# splitter157.net
KiCad netlist of a schematic drawn in EAGLE
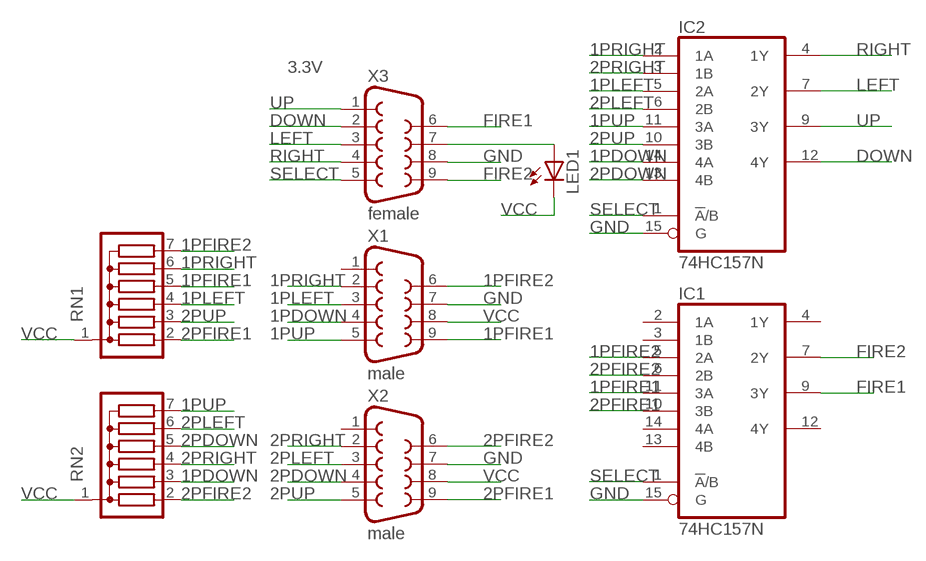
[diagram p0: schematic, sheet 1]

(export (version "E")
  (design (tool "Eeschema 10.0.6"))
  (components
    (comp (ref "IC1")
      (value "74HC157N")
      (footprint "eagle-import:DIL16NUEVO")
      (libsource (lib "eagle-import") (part "74157NHC"))
    )
    (comp (ref "IC2")
      (value "74HC157N")
      (footprint "eagle-import:DIL16NUEVO")
      (libsource (lib "eagle-import") (part "74157NHC"))
    )
    (comp (ref "LED1")
      (value "LED3MM")
      (footprint "eagle-import:LED3MM")
      (libsource (lib "eagle-import") (part "LED3MM"))
    )
    (comp (ref "RN1")
      (value "G06R")
      (footprint "eagle-import:SIL7")
      (libsource (lib "eagle-import") (part "G06R"))
    )
    (comp (ref "RN2")
      (value "G06R")
      (footprint "eagle-import:SIL7")
      (libsource (lib "eagle-import") (part "G06R"))
    )
    (comp (ref "X1")
      (value "male")
      (footprint "eagle-import:F09D")
      (libsource (lib "eagle-import") (part "F09D"))
    )
    (comp (ref "X2")
      (value "male")
      (footprint "eagle-import:F09D")
      (libsource (lib "eagle-import") (part "F09D"))
    )
    (comp (ref "X3")
      (value "female")
      (footprint "eagle-import:F09D")
      (libsource (lib "eagle-import") (part "F09D"))
    )
  )
  (nets
    (net (code "1") (name "/1PDOWN") (class "Default")
      (node (ref "IC2") (pin "14") (pinfunction "4A_14") (pintype "input"))
      (node (ref "RN2") (pin "3") (pinfunction "3_3") (pintype "passive"))
      (node (ref "X1") (pin "4") (pinfunction "4_4") (pintype "passive"))
    )
    (net (code "2") (name "/1PFIRE1") (class "Default")
      (node (ref "IC1") (pin "11") (pinfunction "3A_11") (pintype "input"))
      (node (ref "RN1") (pin "5") (pinfunction "5_5") (pintype "passive"))
      (node (ref "X1") (pin "9") (pinfunction "9_9") (pintype "passive"))
    )
    (net (code "3") (name "/1PFIRE2") (class "Default")
      (node (ref "IC1") (pin "5") (pinfunction "2A_5") (pintype "input"))
      (node (ref "RN1") (pin "7") (pinfunction "7_7") (pintype "passive"))
      (node (ref "X1") (pin "6") (pinfunction "6_6") (pintype "passive"))
    )
    (net (code "4") (name "/1PLEFT") (class "Default")
      (node (ref "IC2") (pin "5") (pinfunction "2A_5") (pintype "input"))
      (node (ref "RN1") (pin "4") (pinfunction "4_4") (pintype "passive"))
      (node (ref "X1") (pin "3") (pinfunction "3_3") (pintype "passive"))
    )
    (net (code "5") (name "/1PRIGHT") (class "Default")
      (node (ref "IC2") (pin "2") (pinfunction "1A_2") (pintype "input"))
      (node (ref "RN1") (pin "6") (pinfunction "6_6") (pintype "passive"))
      (node (ref "X1") (pin "2") (pinfunction "2_2") (pintype "passive"))
    )
    (net (code "6") (name "/1PUP") (class "Default")
      (node (ref "IC2") (pin "11") (pinfunction "3A_11") (pintype "input"))
      (node (ref "RN2") (pin "7") (pinfunction "7_7") (pintype "passive"))
      (node (ref "X1") (pin "5") (pinfunction "5_5") (pintype "passive"))
    )
    (net (code "7") (name "/2PDOWN") (class "Default")
      (node (ref "IC2") (pin "13") (pinfunction "4B_13") (pintype "input"))
      (node (ref "RN2") (pin "5") (pinfunction "5_5") (pintype "passive"))
      (node (ref "X2") (pin "4") (pinfunction "4_4") (pintype "passive"))
    )
    (net (code "8") (name "/2PFIRE1") (class "Default")
      (node (ref "IC1") (pin "10") (pinfunction "3B_10") (pintype "input"))
      (node (ref "RN1") (pin "2") (pinfunction "2_2") (pintype "passive"))
      (node (ref "X2") (pin "9") (pinfunction "9_9") (pintype "passive"))
    )
    (net (code "9") (name "/2PFIRE2") (class "Default")
      (node (ref "IC1") (pin "6") (pinfunction "2B_6") (pintype "input"))
      (node (ref "RN2") (pin "2") (pinfunction "2_2") (pintype "passive"))
      (node (ref "X2") (pin "6") (pinfunction "6_6") (pintype "passive"))
    )
    (net (code "10") (name "/2PLEFT") (class "Default")
      (node (ref "IC2") (pin "6") (pinfunction "2B_6") (pintype "input"))
      (node (ref "RN2") (pin "6") (pinfunction "6_6") (pintype "passive"))
      (node (ref "X2") (pin "3") (pinfunction "3_3") (pintype "passive"))
    )
    (net (code "11") (name "/2PRIGHT") (class "Default")
      (node (ref "IC2") (pin "3") (pinfunction "1B_3") (pintype "input"))
      (node (ref "RN2") (pin "4") (pinfunction "4_4") (pintype "passive"))
      (node (ref "X2") (pin "2") (pinfunction "2_2") (pintype "passive"))
    )
    (net (code "12") (name "/2PUP") (class "Default")
      (node (ref "IC2") (pin "10") (pinfunction "3B_10") (pintype "input"))
      (node (ref "RN1") (pin "3") (pinfunction "3_3") (pintype "passive"))
      (node (ref "X2") (pin "5") (pinfunction "5_5") (pintype "passive"))
    )
    (net (code "14") (name "/DOWN") (class "Default")
      (node (ref "IC2") (pin "12") (pinfunction "4Y_12") (pintype "output"))
      (node (ref "X3") (pin "2") (pinfunction "2_2") (pintype "passive"))
    )
    (net (code "15") (name "/FIRE1") (class "Default")
      (node (ref "IC1") (pin "9") (pinfunction "3Y_9") (pintype "output"))
      (node (ref "X3") (pin "6") (pinfunction "6_6") (pintype "passive"))
    )
    (net (code "16") (name "/FIRE2") (class "Default")
      (node (ref "IC1") (pin "7") (pinfunction "2Y_7") (pintype "output"))
      (node (ref "X3") (pin "9") (pinfunction "9_9") (pintype "passive"))
    )
    (net (code "17") (name "/GND") (class "Default")
      (node (ref "IC1") (pin "15") (pinfunction "G_15") (pintype "input"))
      (node (ref "IC2") (pin "15") (pinfunction "G_15") (pintype "input"))
      (node (ref "X1") (pin "7") (pinfunction "7_7") (pintype "passive"))
      (node (ref "X2") (pin "7") (pinfunction "7_7") (pintype "passive"))
      (node (ref "X3") (pin "8") (pinfunction "8_8") (pintype "passive"))
    )
    (net (code "18") (name "/LEFT") (class "Default")
      (node (ref "IC2") (pin "7") (pinfunction "2Y_7") (pintype "output"))
      (node (ref "X3") (pin "3") (pinfunction "3_3") (pintype "passive"))
    )
    (net (code "19") (name "/RIGHT") (class "Default")
      (node (ref "IC2") (pin "4") (pinfunction "1Y_4") (pintype "output"))
      (node (ref "X3") (pin "4") (pinfunction "4_4") (pintype "passive"))
    )
    (net (code "20") (name "/SELECT") (class "Default")
      (node (ref "IC1") (pin "1") (pinfunction "~{A}/B_1") (pintype "input"))
      (node (ref "IC2") (pin "1") (pinfunction "~{A}/B_1") (pintype "input"))
      (node (ref "X3") (pin "5") (pinfunction "5_5") (pintype "passive"))
    )
    (net (code "21") (name "/UP") (class "Default")
      (node (ref "IC2") (pin "9") (pinfunction "3Y_9") (pintype "output"))
      (node (ref "X3") (pin "1") (pinfunction "1_1") (pintype "passive"))
    )
    (net (code "22") (name "/VCC") (class "Default")
      (node (ref "LED1") (pin "K") (pinfunction "C_K") (pintype "passive"))
      (node (ref "RN1") (pin "1") (pinfunction "1_1") (pintype "passive"))
      (node (ref "RN2") (pin "1") (pinfunction "1_1") (pintype "passive"))
      (node (ref "X1") (pin "8") (pinfunction "8_8") (pintype "passive"))
      (node (ref "X2") (pin "8") (pinfunction "8_8") (pintype "passive"))
    )
    (net (code "23") (name "Net-(LED1-PadA)") (class "Default")
      (node (ref "LED1") (pin "A") (pinfunction "A_A") (pintype "passive"))
      (node (ref "X3") (pin "7") (pinfunction "7_7") (pintype "passive"))
    )
    (net (code "24") (name "unconnected-(IC1A-1A-Pad2)") (class "Default")
      (node (ref "IC1") (pin "2") (pinfunction "1A_2") (pintype "input"))
    )
    (net (code "25") (name "unconnected-(IC1A-1B-Pad3)") (class "Default")
      (node (ref "IC1") (pin "3") (pinfunction "1B_3") (pintype "input"))
    )
    (net (code "26") (name "unconnected-(IC1A-1Y-Pad4)") (class "Default")
      (node (ref "IC1") (pin "4") (pinfunction "1Y_4") (pintype "output"))
    )
    (net (code "27") (name "unconnected-(IC1A-4A-Pad14)") (class "Default")
      (node (ref "IC1") (pin "14") (pinfunction "4A_14") (pintype "input"))
    )
    (net (code "28") (name "unconnected-(IC1A-4B-Pad13)") (class "Default")
      (node (ref "IC1") (pin "13") (pinfunction "4B_13") (pintype "input"))
    )
    (net (code "29") (name "unconnected-(IC1A-4Y-Pad12)") (class "Default")
      (node (ref "IC1") (pin "12") (pinfunction "4Y_12") (pintype "output"))
    )
    (net (code "30") (name "unconnected-(X1-Pad1)") (class "Default")
      (node (ref "X1") (pin "1") (pinfunction "1_1") (pintype "passive"))
    )
    (net (code "31") (name "unconnected-(X2-Pad1)") (class "Default")
      (node (ref "X2") (pin "1") (pinfunction "1_1") (pintype "passive"))
    )
  )
)
